# invert.net
KiCad netlist of a schematic drawn in Altium Designer
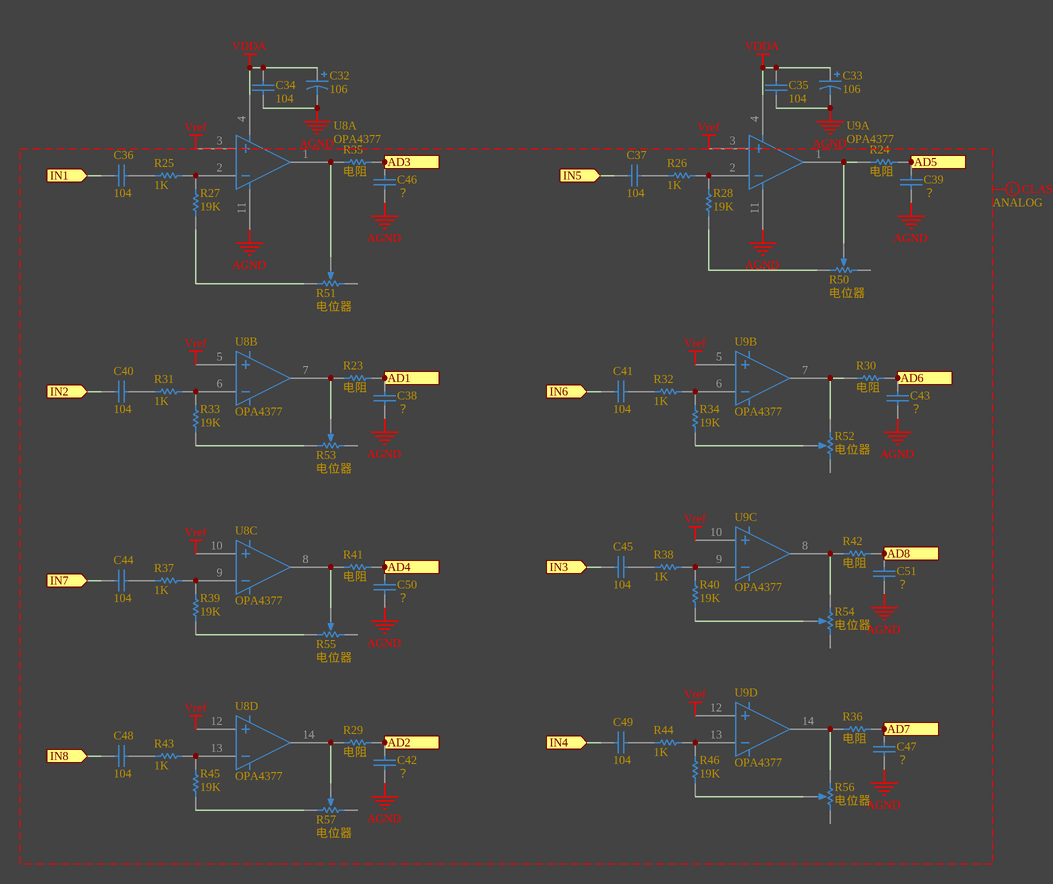
[diagram p0: invert.SchDoc]

(export (version "E")
  (design (tool "Eeschema 10.0.6"))
  (components
    (comp (ref "C32")
      (value "106")
      (footprint "3216-ce")
      (description "Polarized Capacitor (Axial)")
      (fields (field (name "PUBLISHER") "Altium Limited"))
      (libsource (lib "iMag") (part "电解电容"))
    )
    (comp (ref "C33")
      (value "106")
      (footprint "3216-ce")
      (description "Polarized Capacitor (Axial)")
      (fields (field (name "PUBLISHER") "Altium Limited"))
      (libsource (lib "iMag") (part "电解电容"))
    )
    (comp (ref "C34")
      (value "104")
      (footprint "C0402")
      (description "Capacitor")
      (fields (field (name "PUBLISHER") "Altium Limited"))
      (libsource (lib "iMag") (part "电容"))
    )
    (comp (ref "C35")
      (value "104")
      (footprint "C0402")
      (description "Capacitor")
      (fields (field (name "PUBLISHER") "Altium Limited"))
      (libsource (lib "iMag") (part "电容"))
    )
    (comp (ref "C36")
      (value "104")
      (footprint "C0402")
      (description "Capacitor")
      (fields (field (name "PUBLISHER") "Altium Limited"))
      (libsource (lib "iMag") (part "电容"))
    )
    (comp (ref "C37")
      (value "104")
      (footprint "C0402")
      (description "Capacitor")
      (fields (field (name "PUBLISHER") "Altium Limited"))
      (libsource (lib "iMag") (part "电容"))
    )
    (comp (ref "C38")
      (value "？")
      (footprint "C0402")
      (description "Capacitor")
      (fields (field (name "PUBLISHER") "Altium Limited"))
      (libsource (lib "iMag") (part "电容"))
    )
    (comp (ref "C39")
      (value "？")
      (footprint "C0402")
      (description "Capacitor")
      (fields (field (name "PUBLISHER") "Altium Limited"))
      (libsource (lib "iMag") (part "电容"))
    )
    (comp (ref "C40")
      (value "104")
      (footprint "C0402")
      (description "Capacitor")
      (fields (field (name "PUBLISHER") "Altium Limited"))
      (libsource (lib "iMag") (part "电容"))
    )
    (comp (ref "C41")
      (value "104")
      (footprint "C0402")
      (description "Capacitor")
      (fields (field (name "PUBLISHER") "Altium Limited"))
      (libsource (lib "iMag") (part "电容"))
    )
    (comp (ref "C42")
      (value "？")
      (footprint "C0402")
      (description "Capacitor")
      (fields (field (name "PUBLISHER") "Altium Limited"))
      (libsource (lib "iMag") (part "电容"))
    )
    (comp (ref "C43")
      (value "？")
      (footprint "C0402")
      (description "Capacitor")
      (fields (field (name "PUBLISHER") "Altium Limited"))
      (libsource (lib "iMag") (part "电容"))
    )
    (comp (ref "C44")
      (value "104")
      (footprint "C0402")
      (description "Capacitor")
      (fields (field (name "PUBLISHER") "Altium Limited"))
      (libsource (lib "iMag") (part "电容"))
    )
    (comp (ref "C45")
      (value "104")
      (footprint "C0402")
      (description "Capacitor")
      (fields (field (name "PUBLISHER") "Altium Limited"))
      (libsource (lib "iMag") (part "电容"))
    )
    (comp (ref "C46")
      (value "？")
      (footprint "C0402")
      (description "Capacitor")
      (fields (field (name "PUBLISHER") "Altium Limited"))
      (libsource (lib "iMag") (part "电容"))
    )
    (comp (ref "C47")
      (value "？")
      (footprint "C0402")
      (description "Capacitor")
      (fields (field (name "PUBLISHER") "Altium Limited"))
      (libsource (lib "iMag") (part "电容"))
    )
    (comp (ref "C48")
      (value "104")
      (footprint "C0402")
      (description "Capacitor")
      (fields (field (name "PUBLISHER") "Altium Limited"))
      (libsource (lib "iMag") (part "电容"))
    )
    (comp (ref "C49")
      (value "104")
      (footprint "C0402")
      (description "Capacitor")
      (fields (field (name "PUBLISHER") "Altium Limited"))
      (libsource (lib "iMag") (part "电容"))
    )
    (comp (ref "C50")
      (value "？")
      (footprint "C0402")
      (description "Capacitor")
      (fields (field (name "PUBLISHER") "Altium Limited"))
      (libsource (lib "iMag") (part "电容"))
    )
    (comp (ref "C51")
      (value "？")
      (footprint "C0402")
      (description "Capacitor")
      (fields (field (name "PUBLISHER") "Altium Limited"))
      (libsource (lib "iMag") (part "电容"))
    )
    (comp (ref "R23")
      (value "电阻")
      (footprint "R0402")
      (description "Resistor")
      (fields (field (name "PUBLISHER") "Altium Limited"))
      (libsource (lib "iMag") (part "电阻"))
    )
    (comp (ref "R24")
      (value "电阻")
      (footprint "R0402")
      (description "Resistor")
      (fields (field (name "PUBLISHER") "Altium Limited"))
      (libsource (lib "iMag") (part "电阻"))
    )
    (comp (ref "R25")
      (value "1K")
      (footprint "R0402")
      (description "Resistor")
      (fields (field (name "PUBLISHER") "Altium Limited"))
      (libsource (lib "iMag") (part "电阻"))
    )
    (comp (ref "R26")
      (value "1K")
      (footprint "R0402")
      (description "Resistor")
      (fields (field (name "PUBLISHER") "Altium Limited"))
      (libsource (lib "iMag") (part "电阻"))
    )
    (comp (ref "R27")
      (value "19K")
      (footprint "R0402")
      (description "Resistor")
      (fields (field (name "PUBLISHER") "Altium Limited"))
      (libsource (lib "iMag") (part "电阻"))
    )
    (comp (ref "R28")
      (value "19K")
      (footprint "R0402")
      (description "Resistor")
      (fields (field (name "PUBLISHER") "Altium Limited"))
      (libsource (lib "iMag") (part "电阻"))
    )
    (comp (ref "R29")
      (value "电阻")
      (footprint "R0402")
      (description "Resistor")
      (fields (field (name "PUBLISHER") "Altium Limited"))
      (libsource (lib "iMag") (part "电阻"))
    )
    (comp (ref "R30")
      (value "电阻")
      (footprint "R0402")
      (description "Resistor")
      (fields (field (name "PUBLISHER") "Altium Limited"))
      (libsource (lib "iMag") (part "电阻"))
    )
    (comp (ref "R31")
      (value "1K")
      (footprint "R0402")
      (description "Resistor")
      (fields (field (name "PUBLISHER") "Altium Limited"))
      (libsource (lib "iMag") (part "电阻"))
    )
    (comp (ref "R32")
      (value "1K")
      (footprint "R0402")
      (description "Resistor")
      (fields (field (name "PUBLISHER") "Altium Limited"))
      (libsource (lib "iMag") (part "电阻"))
    )
    (comp (ref "R33")
      (value "19K")
      (footprint "R0402")
      (description "Resistor")
      (fields (field (name "PUBLISHER") "Altium Limited"))
      (libsource (lib "iMag") (part "电阻"))
    )
    (comp (ref "R34")
      (value "19K")
      (footprint "R0402")
      (description "Resistor")
      (fields (field (name "PUBLISHER") "Altium Limited"))
      (libsource (lib "iMag") (part "电阻"))
    )
    (comp (ref "R35")
      (value "电阻")
      (footprint "R0402")
      (description "Resistor")
      (fields (field (name "PUBLISHER") "Altium Limited"))
      (libsource (lib "iMag") (part "电阻"))
    )
    (comp (ref "R36")
      (value "电阻")
      (footprint "R0402")
      (description "Resistor")
      (fields (field (name "PUBLISHER") "Altium Limited"))
      (libsource (lib "iMag") (part "电阻"))
    )
    (comp (ref "R37")
      (value "1K")
      (footprint "R0402")
      (description "Resistor")
      (fields (field (name "PUBLISHER") "Altium Limited"))
      (libsource (lib "iMag") (part "电阻"))
    )
    (comp (ref "R38")
      (value "1K")
      (footprint "R0402")
      (description "Resistor")
      (fields (field (name "PUBLISHER") "Altium Limited"))
      (libsource (lib "iMag") (part "电阻"))
    )
    (comp (ref "R39")
      (value "19K")
      (footprint "R0402")
      (description "Resistor")
      (fields (field (name "PUBLISHER") "Altium Limited"))
      (libsource (lib "iMag") (part "电阻"))
    )
    (comp (ref "R40")
      (value "19K")
      (footprint "R0402")
      (description "Resistor")
      (fields (field (name "PUBLISHER") "Altium Limited"))
      (libsource (lib "iMag") (part "电阻"))
    )
    (comp (ref "R41")
      (value "电阻")
      (footprint "R0402")
      (description "Resistor")
      (fields (field (name "PUBLISHER") "Altium Limited"))
      (libsource (lib "iMag") (part "电阻"))
    )
    (comp (ref "R42")
      (value "电阻")
      (footprint "R0402")
      (description "Resistor")
      (fields (field (name "PUBLISHER") "Altium Limited"))
      (libsource (lib "iMag") (part "电阻"))
    )
    (comp (ref "R43")
      (value "1K")
      (footprint "R0402")
      (description "Resistor")
      (fields (field (name "PUBLISHER") "Altium Limited"))
      (libsource (lib "iMag") (part "电阻"))
    )
    (comp (ref "R44")
      (value "1K")
      (footprint "R0402")
      (description "Resistor")
      (fields (field (name "PUBLISHER") "Altium Limited"))
      (libsource (lib "iMag") (part "电阻"))
    )
    (comp (ref "R45")
      (value "19K")
      (footprint "R0402")
      (description "Resistor")
      (fields (field (name "PUBLISHER") "Altium Limited"))
      (libsource (lib "iMag") (part "电阻"))
    )
    (comp (ref "R46")
      (value "19K")
      (footprint "R0402")
      (description "Resistor")
      (fields (field (name "PUBLISHER") "Altium Limited"))
      (libsource (lib "iMag") (part "电阻"))
    )
    (comp (ref "R50") (value "电位器") (footprint "3296W") (libsource (lib "iMag") (part "电位器")))
    (comp (ref "R51") (value "电位器") (footprint "3296W") (libsource (lib "iMag") (part "电位器")))
    (comp (ref "R52") (value "电位器") (footprint "3296W") (libsource (lib "iMag") (part "电位器")))
    (comp (ref "R53") (value "电位器") (footprint "3296W") (libsource (lib "iMag") (part "电位器")))
    (comp (ref "R54") (value "电位器") (footprint "3296W") (libsource (lib "iMag") (part "电位器")))
    (comp (ref "R55") (value "电位器") (footprint "3296W") (libsource (lib "iMag") (part "电位器")))
    (comp (ref "R56") (value "电位器") (footprint "3296W") (libsource (lib "iMag") (part "电位器")))
    (comp (ref "R57") (value "电位器") (footprint "3296W") (libsource (lib "iMag") (part "电位器")))
    (comp (ref "U8") (value "OPA4377") (footprint "TSSOP-14") (libsource (lib "iMag") (part "4运放")))
    (comp (ref "U9") (value "OPA4377") (footprint "TSSOP-14") (libsource (lib "iMag") (part "4运放")))
  )
  (nets
    (net (code "1") (name "/AD1") (class "Default")
      (node (ref "C38") (pin "2") (pinfunction "2_2") (pintype "passive"))
      (node (ref "R23") (pin "1") (pinfunction "1_1") (pintype "passive"))
    )
    (net (code "2") (name "/AD2") (class "Default")
      (node (ref "C42") (pin "2") (pinfunction "2_2") (pintype "passive"))
      (node (ref "R29") (pin "1") (pinfunction "1_1") (pintype "passive"))
    )
    (net (code "3") (name "/AD3") (class "Default")
      (node (ref "C46") (pin "2") (pinfunction "2_2") (pintype "passive"))
      (node (ref "R35") (pin "1") (pinfunction "1_1") (pintype "passive"))
    )
    (net (code "4") (name "/AD4") (class "Default")
      (node (ref "C50") (pin "2") (pinfunction "2_2") (pintype "passive"))
      (node (ref "R41") (pin "1") (pinfunction "1_1") (pintype "passive"))
    )
    (net (code "5") (name "/AD5") (class "Default")
      (node (ref "C39") (pin "2") (pinfunction "2_2") (pintype "passive"))
      (node (ref "R24") (pin "1") (pinfunction "1_1") (pintype "passive"))
    )
    (net (code "6") (name "/AD6") (class "Default")
      (node (ref "C43") (pin "2") (pinfunction "2_2") (pintype "passive"))
      (node (ref "R30") (pin "1") (pinfunction "1_1") (pintype "passive"))
    )
    (net (code "7") (name "/AD7") (class "Default")
      (node (ref "C47") (pin "2") (pinfunction "2_2") (pintype "passive"))
      (node (ref "R36") (pin "1") (pinfunction "1_1") (pintype "passive"))
    )
    (net (code "8") (name "/AD8") (class "Default")
      (node (ref "C51") (pin "2") (pinfunction "2_2") (pintype "passive"))
      (node (ref "R42") (pin "1") (pinfunction "1_1") (pintype "passive"))
    )
    (net (code "9") (name "/IN1") (class "Default")
      (node (ref "C36") (pin "1") (pinfunction "1_1") (pintype "passive"))
    )
    (net (code "10") (name "/IN2") (class "Default")
      (node (ref "C40") (pin "1") (pinfunction "1_1") (pintype "passive"))
    )
    (net (code "11") (name "/IN3") (class "Default")
      (node (ref "C45") (pin "1") (pinfunction "1_1") (pintype "passive"))
    )
    (net (code "12") (name "/IN4") (class "Default")
      (node (ref "C49") (pin "1") (pinfunction "1_1") (pintype "passive"))
    )
    (net (code "13") (name "/IN5") (class "Default")
      (node (ref "C37") (pin "1") (pinfunction "1_1") (pintype "passive"))
    )
    (net (code "14") (name "/IN6") (class "Default")
      (node (ref "C41") (pin "1") (pinfunction "1_1") (pintype "passive"))
    )
    (net (code "15") (name "/IN7") (class "Default")
      (node (ref "C44") (pin "1") (pinfunction "1_1") (pintype "passive"))
    )
    (net (code "16") (name "/IN8") (class "Default")
      (node (ref "C48") (pin "1") (pinfunction "1_1") (pintype "passive"))
    )
    (net (code "17") (name "AGND") (class "Default")
      (node (ref "C32") (pin "2") (pinfunction "2_2") (pintype "passive"))
      (node (ref "C33") (pin "2") (pinfunction "2_2") (pintype "passive"))
      (node (ref "C34") (pin "1") (pinfunction "1_1") (pintype "passive"))
      (node (ref "C35") (pin "1") (pinfunction "1_1") (pintype "passive"))
      (node (ref "C38") (pin "1") (pinfunction "1_1") (pintype "passive"))
      (node (ref "C39") (pin "1") (pinfunction "1_1") (pintype "passive"))
      (node (ref "C42") (pin "1") (pinfunction "1_1") (pintype "passive"))
      (node (ref "C43") (pin "1") (pinfunction "1_1") (pintype "passive"))
      (node (ref "C46") (pin "1") (pinfunction "1_1") (pintype "passive"))
      (node (ref "C47") (pin "1") (pinfunction "1_1") (pintype "passive"))
      (node (ref "C50") (pin "1") (pinfunction "1_1") (pintype "passive"))
      (node (ref "C51") (pin "1") (pinfunction "1_1") (pintype "passive"))
      (node (ref "U8") (pin "11") (pintype "passive"))
      (node (ref "U9") (pin "11") (pintype "passive"))
    )
    (net (code "18") (name "Net-(C36-Pad2)") (class "Default")
      (node (ref "C36") (pin "2") (pinfunction "2_2") (pintype "passive"))
      (node (ref "R25") (pin "2") (pinfunction "2_2") (pintype "passive"))
    )
    (net (code "19") (name "Net-(C37-Pad2)") (class "Default")
      (node (ref "C37") (pin "2") (pinfunction "2_2") (pintype "passive"))
      (node (ref "R26") (pin "2") (pinfunction "2_2") (pintype "passive"))
    )
    (net (code "20") (name "Net-(C40-Pad2)") (class "Default")
      (node (ref "C40") (pin "2") (pinfunction "2_2") (pintype "passive"))
      (node (ref "R31") (pin "2") (pinfunction "2_2") (pintype "passive"))
    )
    (net (code "21") (name "Net-(C41-Pad2)") (class "Default")
      (node (ref "C41") (pin "2") (pinfunction "2_2") (pintype "passive"))
      (node (ref "R32") (pin "2") (pinfunction "2_2") (pintype "passive"))
    )
    (net (code "22") (name "Net-(C44-Pad2)") (class "Default")
      (node (ref "C44") (pin "2") (pinfunction "2_2") (pintype "passive"))
      (node (ref "R37") (pin "2") (pinfunction "2_2") (pintype "passive"))
    )
    (net (code "23") (name "Net-(C45-Pad2)") (class "Default")
      (node (ref "C45") (pin "2") (pinfunction "2_2") (pintype "passive"))
      (node (ref "R38") (pin "2") (pinfunction "2_2") (pintype "passive"))
    )
    (net (code "24") (name "Net-(C48-Pad2)") (class "Default")
      (node (ref "C48") (pin "2") (pinfunction "2_2") (pintype "passive"))
      (node (ref "R43") (pin "2") (pinfunction "2_2") (pintype "passive"))
    )
    (net (code "25") (name "Net-(C49-Pad2)") (class "Default")
      (node (ref "C49") (pin "2") (pinfunction "2_2") (pintype "passive"))
      (node (ref "R44") (pin "2") (pinfunction "2_2") (pintype "passive"))
    )
    (net (code "26") (name "Net-(R25-Pad1)") (class "Default")
      (node (ref "R25") (pin "1") (pinfunction "1_1") (pintype "passive"))
      (node (ref "R27") (pin "1") (pinfunction "1_1") (pintype "passive"))
      (node (ref "U8") (pin "2") (pintype "passive"))
    )
    (net (code "27") (name "Net-(R26-Pad1)") (class "Default")
      (node (ref "R26") (pin "1") (pinfunction "1_1") (pintype "passive"))
      (node (ref "R28") (pin "1") (pinfunction "1_1") (pintype "passive"))
      (node (ref "U9") (pin "2") (pintype "passive"))
    )
    (net (code "28") (name "Net-(R31-Pad1)") (class "Default")
      (node (ref "R31") (pin "1") (pinfunction "1_1") (pintype "passive"))
      (node (ref "R33") (pin "1") (pinfunction "1_1") (pintype "passive"))
      (node (ref "U8") (pin "6") (pintype "passive"))
    )
    (net (code "29") (name "Net-(R32-Pad1)") (class "Default")
      (node (ref "R32") (pin "1") (pinfunction "1_1") (pintype "passive"))
      (node (ref "R34") (pin "1") (pinfunction "1_1") (pintype "passive"))
      (node (ref "U9") (pin "6") (pintype "passive"))
    )
    (net (code "30") (name "Net-(R37-Pad1)") (class "Default")
      (node (ref "R37") (pin "1") (pinfunction "1_1") (pintype "passive"))
      (node (ref "R39") (pin "1") (pinfunction "1_1") (pintype "passive"))
      (node (ref "U8") (pin "9") (pintype "passive"))
    )
    (net (code "31") (name "Net-(R38-Pad1)") (class "Default")
      (node (ref "R38") (pin "1") (pinfunction "1_1") (pintype "passive"))
      (node (ref "R40") (pin "1") (pinfunction "1_1") (pintype "passive"))
      (node (ref "U9") (pin "9") (pintype "passive"))
    )
    (net (code "32") (name "Net-(R43-Pad1)") (class "Default")
      (node (ref "R43") (pin "1") (pinfunction "1_1") (pintype "passive"))
      (node (ref "R45") (pin "1") (pinfunction "1_1") (pintype "passive"))
      (node (ref "U8") (pin "13") (pintype "passive"))
    )
    (net (code "33") (name "Net-(R44-Pad1)") (class "Default")
      (node (ref "R44") (pin "1") (pinfunction "1_1") (pintype "passive"))
      (node (ref "R46") (pin "1") (pinfunction "1_1") (pintype "passive"))
      (node (ref "U9") (pin "13") (pintype "passive"))
    )
    (net (code "34") (name "Net-(R50-BOT)") (class "Default")
      (node (ref "R28") (pin "2") (pinfunction "2_2") (pintype "passive"))
      (node (ref "R50") (pin "3") (pinfunction "BOT_3") (pintype "passive"))
    )
    (net (code "35") (name "Net-(R50-TAP)") (class "Default")
      (node (ref "R24") (pin "2") (pinfunction "2_2") (pintype "passive"))
      (node (ref "R50") (pin "2") (pinfunction "TAP_2") (pintype "passive"))
      (node (ref "U9") (pin "1") (pintype "passive"))
    )
    (net (code "36") (name "Net-(R51-BOT)") (class "Default")
      (node (ref "R27") (pin "2") (pinfunction "2_2") (pintype "passive"))
      (node (ref "R51") (pin "3") (pinfunction "BOT_3") (pintype "passive"))
    )
    (net (code "37") (name "Net-(R51-TAP)") (class "Default")
      (node (ref "R35") (pin "2") (pinfunction "2_2") (pintype "passive"))
      (node (ref "R51") (pin "2") (pinfunction "TAP_2") (pintype "passive"))
      (node (ref "U8") (pin "1") (pintype "passive"))
    )
    (net (code "38") (name "Net-(R52-TAP)") (class "Default")
      (node (ref "R34") (pin "2") (pinfunction "2_2") (pintype "passive"))
      (node (ref "R52") (pin "2") (pinfunction "TAP_2") (pintype "passive"))
    )
    (net (code "39") (name "Net-(R52-TOP)") (class "Default")
      (node (ref "R30") (pin "2") (pinfunction "2_2") (pintype "passive"))
      (node (ref "R52") (pin "1") (pinfunction "TOP_1") (pintype "passive"))
      (node (ref "U9") (pin "7") (pintype "passive"))
    )
    (net (code "40") (name "Net-(R53-BOT)") (class "Default")
      (node (ref "R33") (pin "2") (pinfunction "2_2") (pintype "passive"))
      (node (ref "R53") (pin "3") (pinfunction "BOT_3") (pintype "passive"))
    )
    (net (code "41") (name "Net-(R53-TAP)") (class "Default")
      (node (ref "R23") (pin "2") (pinfunction "2_2") (pintype "passive"))
      (node (ref "R53") (pin "2") (pinfunction "TAP_2") (pintype "passive"))
      (node (ref "U8") (pin "7") (pintype "passive"))
    )
    (net (code "42") (name "Net-(R54-TAP)") (class "Default")
      (node (ref "R40") (pin "2") (pinfunction "2_2") (pintype "passive"))
      (node (ref "R54") (pin "2") (pinfunction "TAP_2") (pintype "passive"))
    )
    (net (code "43") (name "Net-(R54-TOP)") (class "Default")
      (node (ref "R42") (pin "2") (pinfunction "2_2") (pintype "passive"))
      (node (ref "R54") (pin "1") (pinfunction "TOP_1") (pintype "passive"))
      (node (ref "U9") (pin "8") (pintype "passive"))
    )
    (net (code "44") (name "Net-(R55-BOT)") (class "Default")
      (node (ref "R39") (pin "2") (pinfunction "2_2") (pintype "passive"))
      (node (ref "R55") (pin "3") (pinfunction "BOT_3") (pintype "passive"))
    )
    (net (code "45") (name "Net-(R55-TAP)") (class "Default")
      (node (ref "R41") (pin "2") (pinfunction "2_2") (pintype "passive"))
      (node (ref "R55") (pin "2") (pinfunction "TAP_2") (pintype "passive"))
      (node (ref "U8") (pin "8") (pintype "passive"))
    )
    (net (code "46") (name "Net-(R56-TAP)") (class "Default")
      (node (ref "R46") (pin "2") (pinfunction "2_2") (pintype "passive"))
      (node (ref "R56") (pin "2") (pinfunction "TAP_2") (pintype "passive"))
    )
    (net (code "47") (name "Net-(R56-TOP)") (class "Default")
      (node (ref "R36") (pin "2") (pinfunction "2_2") (pintype "passive"))
      (node (ref "R56") (pin "1") (pinfunction "TOP_1") (pintype "passive"))
      (node (ref "U9") (pin "14") (pintype "passive"))
    )
    (net (code "48") (name "Net-(R57-BOT)") (class "Default")
      (node (ref "R45") (pin "2") (pinfunction "2_2") (pintype "passive"))
      (node (ref "R57") (pin "3") (pinfunction "BOT_3") (pintype "passive"))
    )
    (net (code "49") (name "Net-(R57-TAP)") (class "Default")
      (node (ref "R29") (pin "2") (pinfunction "2_2") (pintype "passive"))
      (node (ref "R57") (pin "2") (pinfunction "TAP_2") (pintype "passive"))
      (node (ref "U8") (pin "14") (pintype "passive"))
    )
    (net (code "50") (name "VDDA") (class "Default")
      (node (ref "C32") (pin "1") (pinfunction "1_1") (pintype "passive"))
      (node (ref "C33") (pin "1") (pinfunction "1_1") (pintype "passive"))
      (node (ref "C34") (pin "2") (pinfunction "2_2") (pintype "passive"))
      (node (ref "C35") (pin "2") (pinfunction "2_2") (pintype "passive"))
      (node (ref "U8") (pin "4") (pintype "passive"))
      (node (ref "U9") (pin "4") (pintype "passive"))
    )
    (net (code "51") (name "Vref") (class "Default")
      (node (ref "U8") (pin "10") (pintype "passive"))
      (node (ref "U8") (pin "12") (pintype "passive"))
      (node (ref "U8") (pin "3") (pintype "passive"))
      (node (ref "U8") (pin "5") (pintype "passive"))
      (node (ref "U9") (pin "10") (pintype "passive"))
      (node (ref "U9") (pin "12") (pintype "passive"))
      (node (ref "U9") (pin "3") (pintype "passive"))
      (node (ref "U9") (pin "5") (pintype "passive"))
    )
    (net (code "52") (name "unconnected-(R50-TOP-Pad1)") (class "Default")
      (node (ref "R50") (pin "1") (pinfunction "TOP_1") (pintype "passive"))
    )
    (net (code "53") (name "unconnected-(R51-TOP-Pad1)") (class "Default")
      (node (ref "R51") (pin "1") (pinfunction "TOP_1") (pintype "passive"))
    )
    (net (code "54") (name "unconnected-(R52-BOT-Pad3)") (class "Default")
      (node (ref "R52") (pin "3") (pinfunction "BOT_3") (pintype "passive"))
    )
    (net (code "55") (name "unconnected-(R53-TOP-Pad1)") (class "Default")
      (node (ref "R53") (pin "1") (pinfunction "TOP_1") (pintype "passive"))
    )
    (net (code "56") (name "unconnected-(R54-BOT-Pad3)") (class "Default")
      (node (ref "R54") (pin "3") (pinfunction "BOT_3") (pintype "passive"))
    )
    (net (code "57") (name "unconnected-(R55-TOP-Pad1)") (class "Default")
      (node (ref "R55") (pin "1") (pinfunction "TOP_1") (pintype "passive"))
    )
    (net (code "58") (name "unconnected-(R56-BOT-Pad3)") (class "Default")
      (node (ref "R56") (pin "3") (pinfunction "BOT_3") (pintype "passive"))
    )
    (net (code "59") (name "unconnected-(R57-TOP-Pad1)") (class "Default")
      (node (ref "R57") (pin "1") (pinfunction "TOP_1") (pintype "passive"))
    )
  )
)
